# CAN2.net
KiCad netlist of a schematic drawn in Altium Designer
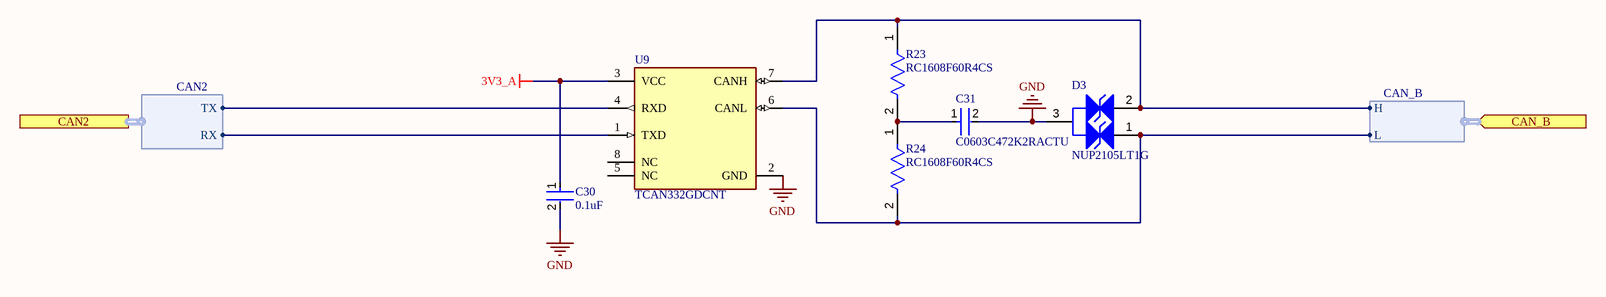
[diagram p0: CAN2.SchDoc]

(export (version "E")
  (design (tool "Eeschema 10.0.6"))
  (components
    (comp (ref "C30")
      (value "0.1uF")
      (footprint "FP-C0603C-CF-MFG")
      (description "CAP CER 0.1UF 50V X7R 0603")
      (fields (field (name "TOLERANCE") "0.1") (field (name "MANUFACTURER") "KEMET"))
      (libsource (lib "Altium Content Vault") (part "b4654b650e69147ec39a6b967a45e02"))
    )
    (comp (ref "C31")
      (value "C0603C472K2RACTU")
      (footprint "FP-C0603C-CF-MFG")
      (description "CAP CER 4700PF 200V 10% X7R 0603")
      (fields
        (field (name "OCTOPART") "https://octopart.com/c0603c472k2ractu-kemet-17058096")
        (field (name "MANUFACTURER") "KEMET")
      )
      (libsource (lib "Altium Content Vault") (part "b4654b650e69147ec39a6b967a45e02"))
    )
    (comp (ref "D3")
      (value "NUP2105LT1G")
      (footprint "ONSC-SOT-23-3-318-08_V")
      (description "Dual Line CAN Bus Protector, 3-Pin SOT-23, Pb-Free, Tape and Reel")
      (fields (field (name "MANUFACTURER") "On Semiconductor"))
      (libsource (lib "Altium Content Vault") (part "ONSC-NUP21X5X-SOT-23-3-318-08"))
    )
    (comp (ref "R23")
      (value "RC1608F60R4CS")
      (footprint "FP-RC1608-IPC_C")
      (description "Res Thick Film 0603 60.4Ω 1% 0.1W ±100ppm/°C Molded SMD T/R")
      (fields (field (name "TOLERANCE") "1%"))
      (libsource (lib "Altium Content Vault") (part "1029c3af85768c4190bb7ad29bc67b5"))
    )
    (comp (ref "R24")
      (value "RC1608F60R4CS")
      (footprint "FP-RC1608-IPC_C")
      (description "Res Thick Film 0603 60.4Ω 1% 0.1W ±100ppm/°C Molded SMD T/R")
      (fields (field (name "TOLERANCE") "1%"))
      (libsource (lib "Altium Content Vault") (part "1029c3af85768c4190bb7ad29bc67b5"))
    )
    (comp (ref "U9")
      (value "TCAN332GDCNT")
      (footprint "FP-DCN0008A-IPC_C")
      (description "IC TRANSCEIVER 1/1 SOT23-8")
      (libsource (lib "Altium Content Vault") (part "f57d81afad401941ce556981ca48666"))
    )
  )
  (nets
    (net (code "3") (name "/H") (class "Default")
      (node (ref "D3") (pin "2") (pinfunction "K_2") (pintype "passive"))
      (node (ref "R23") (pin "1") (pinfunction "1_1") (pintype "passive"))
      (node (ref "U9") (pin "7") (pinfunction "CANH_7") (pintype "bidirectional"))
    )
    (net (code "4") (name "/L") (class "Default")
      (node (ref "D3") (pin "1") (pinfunction "K_1") (pintype "passive"))
      (node (ref "R24") (pin "2") (pinfunction "2_2") (pintype "passive"))
      (node (ref "U9") (pin "6") (pinfunction "CANL_6") (pintype "bidirectional"))
    )
    (net (code "5") (name "/RX") (class "Default")
      (node (ref "U9") (pin "1") (pinfunction "TXD_1") (pintype "input"))
    )
    (net (code "6") (name "/TX") (class "Default")
      (node (ref "U9") (pin "4") (pinfunction "RXD_4") (pintype "output"))
    )
    (net (code "9") (name "3V3_A") (class "Default")
      (node (ref "C30") (pin "1") (pinfunction "1_1") (pintype "passive"))
      (node (ref "U9") (pin "3") (pinfunction "VCC_3") (pintype "power_in"))
    )
    (net (code "10") (name "GND") (class "Default")
      (node (ref "C30") (pin "2") (pinfunction "2_2") (pintype "passive"))
      (node (ref "C31") (pin "2") (pinfunction "2_2") (pintype "passive"))
      (node (ref "D3") (pin "3") (pinfunction "K_3") (pintype "passive"))
      (node (ref "U9") (pin "2") (pinfunction "GND_2") (pintype "power_in"))
    )
    (net (code "11") (name "Net-(C31-Pad1)") (class "Default")
      (node (ref "C31") (pin "1") (pinfunction "1_1") (pintype "passive"))
      (node (ref "R23") (pin "2") (pinfunction "2_2") (pintype "passive"))
      (node (ref "R24") (pin "1") (pinfunction "1_1") (pintype "passive"))
    )
    (net (code "12") (name "unconnected-(U9-NC-Pad5)") (class "Default")
      (node (ref "U9") (pin "5") (pinfunction "NC_5") (pintype "passive"))
    )
    (net (code "13") (name "unconnected-(U9-NC-Pad8)") (class "Default")
      (node (ref "U9") (pin "8") (pinfunction "NC_8") (pintype "passive"))
    )
  )
)
